# MC24LC512Shield.net
KiCad netlist of a schematic drawn in EAGLE
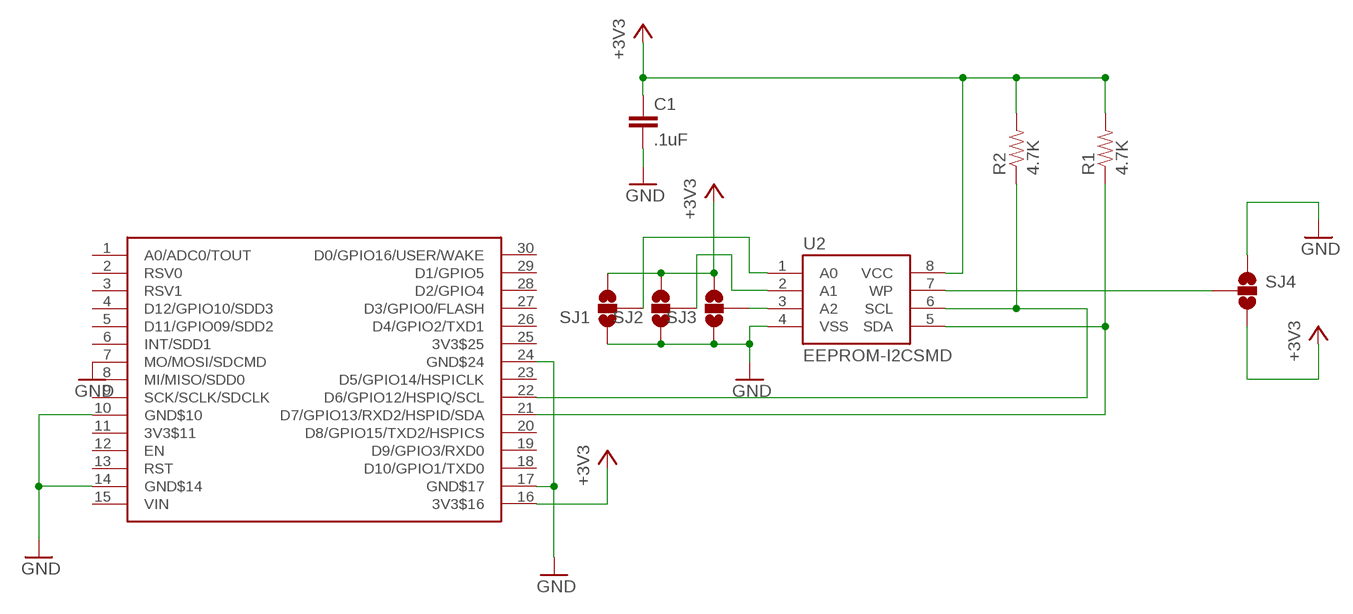
[diagram p0: schematic, sheet 1]

(export (version "E")
  (design (tool "Eeschema 10.0.6"))
  (components
    (comp (ref "C1")
      (value ".1uF")
      (footprint "eagle-import:0603-CAP")
      (libsource (lib "eagle-import") (part "CAP0603-CAP"))
    )
    (comp (ref "R1")
      (value "4.7K")
      (footprint "eagle-import:0603-RES")
      (libsource (lib "eagle-import") (part "RESISTOR0603-RES"))
    )
    (comp (ref "R2")
      (value "4.7K")
      (footprint "eagle-import:0603-RES")
      (libsource (lib "eagle-import") (part "RESISTOR0603-RES"))
    )
    (comp (ref "SJ1")
      (value "SOLDERJUMPER_2WAYPASTE1&2")
      (footprint "eagle-import:SJ_3_PASTE1&2")
      (libsource (lib "eagle-import") (part "SOLDERJUMPER_2WAYPASTE1&2"))
    )
    (comp (ref "SJ2")
      (value "SOLDERJUMPER_2WAYPASTE1&2")
      (footprint "eagle-import:SJ_3_PASTE1&2")
      (libsource (lib "eagle-import") (part "SOLDERJUMPER_2WAYPASTE1&2"))
    )
    (comp (ref "SJ3")
      (value "SOLDERJUMPER_2WAYPASTE1&2")
      (footprint "eagle-import:SJ_3_PASTE1&2")
      (libsource (lib "eagle-import") (part "SOLDERJUMPER_2WAYPASTE1&2"))
    )
    (comp (ref "SJ4")
      (value "SOLDERJUMPER_2WAYPASTE1&2")
      (footprint "eagle-import:SJ_3_PASTE1&2")
      (libsource (lib "eagle-import") (part "SOLDERJUMPER_2WAYPASTE1&2"))
    )
    (comp (ref "U$2")
      (value "NERDSHIELD")
      (footprint "eagle-import:NERDUINO_STACK")
      (libsource (lib "eagle-import") (part "NERDSHIELD"))
    )
    (comp (ref "U2")
      (value "EEPROM-I2CSMD")
      (footprint "eagle-import:SO08")
      (libsource (lib "eagle-import") (part "EEPROM-I2CSMD"))
    )
  )
  (nets
    (net (code "1") (name "+3V3") (class "Default")
      (node (ref "C1") (pin "1") (pinfunction "1_1") (pintype "passive"))
      (node (ref "R1") (pin "2") (pinfunction "2_2") (pintype "passive"))
      (node (ref "R2") (pin "2") (pinfunction "2_2") (pintype "passive"))
      (node (ref "SJ1") (pin "3") (pinfunction "3_3") (pintype "passive"))
      (node (ref "SJ2") (pin "3") (pinfunction "3_3") (pintype "passive"))
      (node (ref "SJ3") (pin "3") (pinfunction "3_3") (pintype "passive"))
      (node (ref "SJ4") (pin "3") (pinfunction "3_3") (pintype "passive"))
      (node (ref "U$2") (pin "16") (pinfunction "3V3$16_16") (pintype "bidirectional"))
      (node (ref "U2") (pin "8") (pinfunction "VCC_8") (pintype "power_in"))
    )
    (net (code "2") (name "GND") (class "Default")
      (node (ref "C1") (pin "2") (pinfunction "2_2") (pintype "passive"))
      (node (ref "SJ1") (pin "1") (pinfunction "1_1") (pintype "passive"))
      (node (ref "SJ2") (pin "1") (pinfunction "1_1") (pintype "passive"))
      (node (ref "SJ3") (pin "1") (pinfunction "1_1") (pintype "passive"))
      (node (ref "SJ4") (pin "1") (pinfunction "1_1") (pintype "passive"))
      (node (ref "U$2") (pin "10") (pinfunction "GND$10_10") (pintype "bidirectional"))
      (node (ref "U$2") (pin "14") (pinfunction "GND$14_14") (pintype "bidirectional"))
      (node (ref "U$2") (pin "17") (pinfunction "GND$17_17") (pintype "bidirectional"))
      (node (ref "U$2") (pin "24") (pinfunction "GND$24_24") (pintype "bidirectional"))
      (node (ref "U$2") (pin "7") (pinfunction "MO/MOSI/SDCMD_7") (pintype "bidirectional"))
      (node (ref "U2") (pin "4") (pinfunction "VSS_4") (pintype "power_in"))
    )
    (net (code "3") (name "Net-(U$2-D6{slash}GPIO12{slash}HSPIQ{slash}SCL)") (class "Default")
      (node (ref "R2") (pin "1") (pinfunction "1_1") (pintype "passive"))
      (node (ref "U$2") (pin "22") (pinfunction "D6/GPIO12/HSPIQ/SCL_22") (pintype "bidirectional"))
      (node (ref "U2") (pin "6") (pinfunction "SCL_6") (pintype "bidirectional"))
    )
    (net (code "4") (name "Net-(U$2-D7{slash}GPIO13{slash}RXD2{slash}HSPID{slash}SDA)") (class "Default")
      (node (ref "R1") (pin "1") (pinfunction "1_1") (pintype "passive"))
      (node (ref "U$2") (pin "21") (pinfunction "D7/GPIO13/RXD2/HSPID/SDA_21") (pintype "bidirectional"))
      (node (ref "U2") (pin "5") (pinfunction "SDA_5") (pintype "bidirectional"))
    )
    (net (code "5") (name "Net-(U2-A0)") (class "Default")
      (node (ref "SJ1") (pin "2") (pinfunction "2_2") (pintype "passive"))
      (node (ref "U2") (pin "1") (pinfunction "A0_1") (pintype "bidirectional"))
    )
    (net (code "6") (name "Net-(U2-A1)") (class "Default")
      (node (ref "SJ2") (pin "2") (pinfunction "2_2") (pintype "passive"))
      (node (ref "U2") (pin "2") (pinfunction "A1_2") (pintype "bidirectional"))
    )
    (net (code "7") (name "Net-(U2-A2)") (class "Default")
      (node (ref "SJ3") (pin "2") (pinfunction "2_2") (pintype "passive"))
      (node (ref "U2") (pin "3") (pinfunction "A2_3") (pintype "bidirectional"))
    )
    (net (code "8") (name "Net-(U2-WP)") (class "Default")
      (node (ref "SJ4") (pin "2") (pinfunction "2_2") (pintype "passive"))
      (node (ref "U2") (pin "7") (pinfunction "WP_7") (pintype "bidirectional"))
    )
    (net (code "9") (name "unconnected-(U$2-3V3$11-Pad11)") (class "Default")
      (node (ref "U$2") (pin "11") (pinfunction "3V3$11_11") (pintype "bidirectional"))
    )
    (net (code "10") (name "unconnected-(U$2-3V3$25-Pad25)") (class "Default")
      (node (ref "U$2") (pin "25") (pinfunction "3V3$25_25") (pintype "bidirectional"))
    )
    (net (code "11") (name "unconnected-(U$2-A0{slash}ADC0{slash}TOUT-Pad1)") (class "Default")
      (node (ref "U$2") (pin "1") (pinfunction "A0/ADC0/TOUT_1") (pintype "bidirectional"))
    )
    (net (code "12") (name "unconnected-(U$2-D0{slash}GPIO16{slash}USER{slash}WAKE-Pad30)") (class "Default")
      (node (ref "U$2") (pin "30") (pinfunction "D0/GPIO16/USER/WAKE_30") (pintype "bidirectional"))
    )
    (net (code "13") (name "unconnected-(U$2-D1{slash}GPIO5-Pad29)") (class "Default")
      (node (ref "U$2") (pin "29") (pinfunction "D1/GPIO5_29") (pintype "bidirectional"))
    )
    (net (code "14") (name "unconnected-(U$2-D2{slash}GPIO4-Pad28)") (class "Default")
      (node (ref "U$2") (pin "28") (pinfunction "D2/GPIO4_28") (pintype "bidirectional"))
    )
    (net (code "15") (name "unconnected-(U$2-D3{slash}GPIO0{slash}FLASH-Pad27)") (class "Default")
      (node (ref "U$2") (pin "27") (pinfunction "D3/GPIO0/FLASH_27") (pintype "bidirectional"))
    )
    (net (code "16") (name "unconnected-(U$2-D4{slash}GPIO2{slash}TXD1-Pad26)") (class "Default")
      (node (ref "U$2") (pin "26") (pinfunction "D4/GPIO2/TXD1_26") (pintype "bidirectional"))
    )
    (net (code "17") (name "unconnected-(U$2-D5{slash}GPIO14{slash}HSPICLK-Pad23)") (class "Default")
      (node (ref "U$2") (pin "23") (pinfunction "D5/GPIO14/HSPICLK_23") (pintype "bidirectional"))
    )
    (net (code "18") (name "unconnected-(U$2-D8{slash}GPIO15{slash}TXD2{slash}HSPICS-Pad20)") (class "Default")
      (node (ref "U$2") (pin "20") (pinfunction "D8/GPIO15/TXD2/HSPICS_20") (pintype "bidirectional"))
    )
    (net (code "19") (name "unconnected-(U$2-D9{slash}GPIO3{slash}RXD0-Pad19)") (class "Default")
      (node (ref "U$2") (pin "19") (pinfunction "D9/GPIO3/RXD0_19") (pintype "bidirectional"))
    )
    (net (code "20") (name "unconnected-(U$2-D10{slash}GPIO1{slash}TXD0-Pad18)") (class "Default")
      (node (ref "U$2") (pin "18") (pinfunction "D10/GPIO1/TXD0_18") (pintype "bidirectional"))
    )
    (net (code "21") (name "unconnected-(U$2-D11{slash}GPIO09{slash}SDD2-Pad5)") (class "Default")
      (node (ref "U$2") (pin "5") (pinfunction "D11/GPIO09/SDD2_5") (pintype "bidirectional"))
    )
    (net (code "22") (name "unconnected-(U$2-D12{slash}GPIO10{slash}SDD3-Pad4)") (class "Default")
      (node (ref "U$2") (pin "4") (pinfunction "D12/GPIO10/SDD3_4") (pintype "bidirectional"))
    )
    (net (code "23") (name "unconnected-(U$2-EN-Pad12)") (class "Default")
      (node (ref "U$2") (pin "12") (pinfunction "EN_12") (pintype "bidirectional"))
    )
    (net (code "24") (name "unconnected-(U$2-INT{slash}SDD1-Pad6)") (class "Default")
      (node (ref "U$2") (pin "6") (pinfunction "INT/SDD1_6") (pintype "bidirectional"))
    )
    (net (code "25") (name "unconnected-(U$2-MI{slash}MISO{slash}SDD0-Pad8)") (class "Default")
      (node (ref "U$2") (pin "8") (pinfunction "MI/MISO/SDD0_8") (pintype "bidirectional"))
    )
    (net (code "26") (name "unconnected-(U$2-RST-Pad13)") (class "Default")
      (node (ref "U$2") (pin "13") (pinfunction "RST_13") (pintype "bidirectional"))
    )
    (net (code "27") (name "unconnected-(U$2-RSV0-Pad2)") (class "Default")
      (node (ref "U$2") (pin "2") (pinfunction "RSV0_2") (pintype "bidirectional"))
    )
    (net (code "28") (name "unconnected-(U$2-RSV1-Pad3)") (class "Default")
      (node (ref "U$2") (pin "3") (pinfunction "RSV1_3") (pintype "bidirectional"))
    )
    (net (code "29") (name "unconnected-(U$2-SCK{slash}SCLK{slash}SDCLK-Pad9)") (class "Default")
      (node (ref "U$2") (pin "9") (pinfunction "SCK/SCLK/SDCLK_9") (pintype "bidirectional"))
    )
    (net (code "30") (name "unconnected-(U$2-VIN-Pad15)") (class "Default")
      (node (ref "U$2") (pin "15") (pinfunction "VIN_15") (pintype "bidirectional"))
    )
  )
)
